# pcb2_0.net
KiCad netlist of a schematic drawn in EAGLE
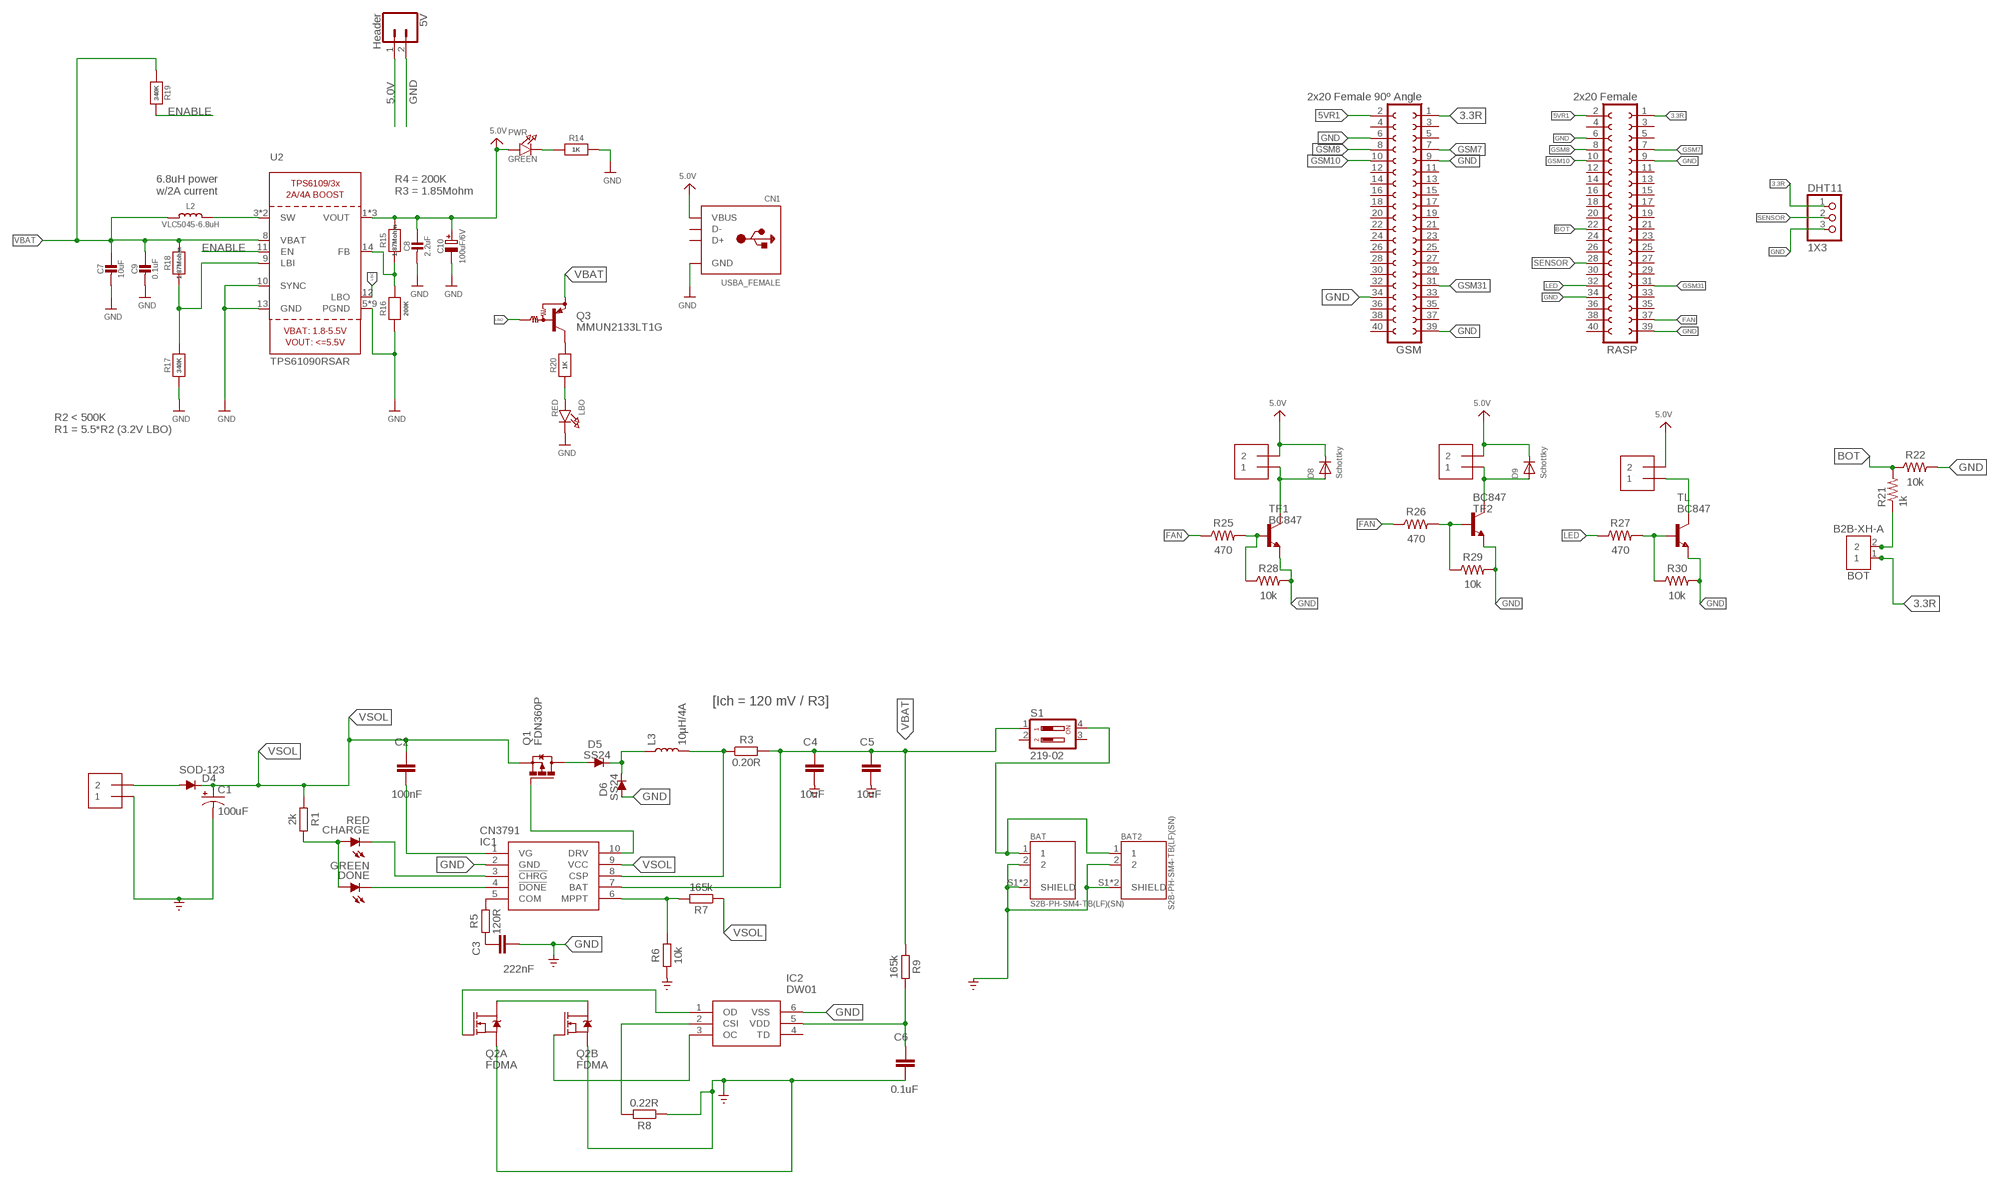
[diagram p0: schematic, sheet 1]

(export (version "E")
  (design (tool "Eeschema 10.0.6"))
  (components
    (comp (ref "5V")
      (value "Header")
      (footprint "eagle-import:1X02")
      (libsource (lib "eagle-import") (part "CONN_02"))
    )
    (comp (ref "BAT")
      (value "S2B-PH-SM4-TB(LF)(SN)")
      (footprint "eagle-import:S2B-PH-SM4-TB(LF)(SN)")
      (fields
        (field (name "DIGI_KEY_PART_NUMBER") "455-1749-1-ND")
        (field (name "MANUFACTURER") "JST Sales America Inc.")
        (field (name "CREATED_BY") "PCBLayout.com")
      )
      (libsource (lib "eagle-import") (part "S2B-PH-SM4-TB(LF)(SN)"))
    )
    (comp (ref "BAT2")
      (value "S2B-PH-SM4-TB(LF)(SN)")
      (footprint "eagle-import:S2B-PH-SM4-TB(LF)(SN)")
      (fields
        (field (name "DIGI_KEY_PART_NUMBER") "455-1749-1-ND")
        (field (name "MANUFACTURER") "JST Sales America Inc.")
        (field (name "CREATED_BY") "PCBLayout.com")
      )
      (libsource (lib "eagle-import") (part "S2B-PH-SM4-TB(LF)(SN)"))
    )
    (comp (ref "BOT")
      (value "B2B-XH-A")
      (footprint "eagle-import:B2B-XH-A")
      (fields (field (name "MANUFACTURER") "JST (XH CONNECTOR)"))
      (libsource (lib "eagle-import") (part "B2B-XH-A"))
    )
    (comp (ref "C1")
      (value "100uF")
      (footprint "eagle-import:153CLV-0505")
      (libsource (lib "eagle-import") (part "CPOL-US153CLV-0505"))
    )
    (comp (ref "C2")
      (value "100nF")
      (footprint "eagle-import:CAP_0603")
      (fields
        (field (name "DIGIKEY_PART_NUMBER") "399-1050-2-ND")
        (field (name "MANUFACTURER") "KEMET")
        (field (name "MPN") "C0603C120J5GACTU")
        (field (name "CREATED_BY") "PCBLayout.com")
      )
      (libsource (lib "eagle-import") (part "C0603C120J5GACTU"))
    )
    (comp (ref "C3")
      (value "222nF")
      (footprint "eagle-import:CAP_0603")
      (fields
        (field (name "DIGIKEY_PART_NUMBER") "399-1050-2-ND")
        (field (name "MANUFACTURER") "KEMET")
        (field (name "MPN") "C0603C120J5GACTU")
        (field (name "CREATED_BY") "PCBLayout.com")
      )
      (libsource (lib "eagle-import") (part "C0603C120J5GACTU"))
    )
    (comp (ref "C4")
      (value "10uF")
      (footprint "eagle-import:CAP_0603")
      (fields
        (field (name "DIGIKEY_PART_NUMBER") "399-1050-2-ND")
        (field (name "MANUFACTURER") "KEMET")
        (field (name "MPN") "C0603C120J5GACTU")
        (field (name "CREATED_BY") "PCBLayout.com")
      )
      (libsource (lib "eagle-import") (part "C0603C120J5GACTU"))
    )
    (comp (ref "C5")
      (value "10uF")
      (footprint "eagle-import:CAP_0603")
      (fields
        (field (name "DIGIKEY_PART_NUMBER") "399-1050-2-ND")
        (field (name "MANUFACTURER") "KEMET")
        (field (name "MPN") "C0603C120J5GACTU")
        (field (name "CREATED_BY") "PCBLayout.com")
      )
      (libsource (lib "eagle-import") (part "C0603C120J5GACTU"))
    )
    (comp (ref "C6")
      (value "0.1uF")
      (footprint "eagle-import:CAP_0603")
      (fields
        (field (name "DIGIKEY_PART_NUMBER") "399-1050-2-ND")
        (field (name "MANUFACTURER") "KEMET")
        (field (name "MPN") "C0603C120J5GACTU")
        (field (name "CREATED_BY") "PCBLayout.com")
      )
      (libsource (lib "eagle-import") (part "C0603C120J5GACTU"))
    )
    (comp (ref "C7")
      (value "10uF")
      (footprint "eagle-import:0805-NO")
      (libsource (lib "eagle-import") (part "CAP_CERAMIC0805-NOOUTLINE"))
    )
    (comp (ref "C8")
      (value "2.2uF")
      (footprint "eagle-import:0805-NO")
      (libsource (lib "eagle-import") (part "CAP_CERAMIC0805-NOOUTLINE"))
    )
    (comp (ref "C9")
      (value "0.1uF")
      (footprint "eagle-import:0805-NO")
      (libsource (lib "eagle-import") (part "CAP_CERAMIC0805-NOOUTLINE"))
    )
    (comp (ref "C10")
      (value "100uF/6V")
      (footprint "eagle-import:EIA3528-21_B-R")
      (libsource (lib "eagle-import") (part "CAP_TANTALUMB/3528_REFLOW"))
    )
    (comp (ref "CHARGE")
      (value "RED")
      (footprint "eagle-import:LED_CHIP-LED0603MP")
      (libsource (lib "eagle-import") (part "LED_LEDCHIP-LED0603MP"))
    )
    (comp (ref "CN1")
      (value "USBA_FEMALE")
      (footprint "eagle-import:USB_HOST-PTH")
      (libsource (lib "eagle-import") (part "USB_TYPEAPTHFML"))
    )
    (comp (ref "D4")
      (value "SOD-123")
      (footprint "eagle-import:DIODE_SOD123")
      (libsource (lib "eagle-import") (part "DIODE_DIODE-SOD123"))
    )
    (comp (ref "D5")
      (value "SS24")
      (footprint "eagle-import:DIODE_SOD123")
      (libsource (lib "eagle-import") (part "DIODE_DIODE-SOD123"))
    )
    (comp (ref "D6")
      (value "SS24")
      (footprint "eagle-import:DIODE_SOD123")
      (libsource (lib "eagle-import") (part "DIODE_DIODE-SOD123"))
    )
    (comp (ref "D8")
      (value "Schottky")
      (footprint "eagle-import:SOD-123")
      (libsource (lib "eagle-import") (part "DIODESOD-123"))
    )
    (comp (ref "D9")
      (value "Schottky")
      (footprint "eagle-import:SOD-123")
      (libsource (lib "eagle-import") (part "DIODESOD-123"))
    )
    (comp (ref "DHT11")
      (value "1X3")
      (footprint "eagle-import:1X03")
      (libsource (lib "eagle-import") (part "PINHD-1X3"))
    )
    (comp (ref "DONE")
      (value "GREEN")
      (footprint "eagle-import:LED_CHIP-LED0603MP")
      (libsource (lib "eagle-import") (part "LED_LEDCHIP-LED0603MP"))
    )
    (comp (ref "FAN1")
      (value "1X2-3.5MM")
      (footprint "eagle-import:1X2-3.5MM")
      (libsource (lib "eagle-import") (part "1X2-3.5MM"))
    )
    (comp (ref "FAN2")
      (value "1X2-3.5MM")
      (footprint "eagle-import:1X2-3.5MM")
      (libsource (lib "eagle-import") (part "1X2-3.5MM"))
    )
    (comp (ref "GSM")
      (value "2x20 Female 90º Angle")
      (footprint "eagle-import:FE20-2W")
      (libsource (lib "eagle-import") (part "FE20-2W"))
    )
    (comp (ref "IC1")
      (value "CN3791")
      (footprint "eagle-import:SOP100P600X175-10N")
      (libsource (lib "eagle-import") (part "CN3791"))
    )
    (comp (ref "IC2")
      (value "DW01")
      (footprint "eagle-import:SOT95P280X135-6N")
      (libsource (lib "eagle-import") (part "DW01"))
    )
    (comp (ref "L2")
      (value "VLC5045-6.8uH")
      (footprint "eagle-import:INDUCTOR_5X5MM_TDK_VLC5045")
      (libsource (lib "eagle-import") (part "INDUCTORTDK_VLC5045"))
    )
    (comp (ref "L3")
      (value "10µH/4A")
      (footprint "eagle-import:CR54")
      (libsource (lib "eagle-import") (part "INDUCTOR-CR54-3.3UH"))
    )
    (comp (ref "LBO")
      (value "RED")
      (footprint "eagle-import:CHIPLED_0805_NOOUTLINE")
      (libsource (lib "eagle-import") (part "LED0805_NOOUTLINE"))
    )
    (comp (ref "LED")
      (value "1X2-3.5MM")
      (footprint "eagle-import:1X2-3.5MM")
      (libsource (lib "eagle-import") (part "1X2-3.5MM"))
    )
    (comp (ref "PWR")
      (value "GREEN")
      (footprint "eagle-import:CHIPLED_0805_NOOUTLINE")
      (libsource (lib "eagle-import") (part "LED0805_NOOUTLINE"))
    )
    (comp (ref "Q1")
      (value "FDN360P")
      (footprint "eagle-import:SUPER-SOT3")
      (libsource (lib "eagle-import") (part "FDN360P"))
    )
    (comp (ref "Q2")
      (value "FDMA")
      (footprint "eagle-import:MICROFET_2X2")
      (libsource (lib "eagle-import") (part "MOSFET_NCH_DUAL-FDMA1024NZ"))
    )
    (comp (ref "Q3")
      (value "MMUN2133LT1G")
      (footprint "eagle-import:SC59-BEC")
      (libsource (lib "eagle-import") (part "-PNP_DRIVER-SC59-BECMUN2114T1"))
    )
    (comp (ref "R1")
      (value "2k")
      (footprint "eagle-import:RESC1608X60")
      (libsource (lib "eagle-import") (part "RCHIP-0603(1608-METRIC)_"))
    )
    (comp (ref "R3")
      (value "0.20R")
      (footprint "eagle-import:RESC1608X60")
      (libsource (lib "eagle-import") (part "RCHIP-0603(1608-METRIC)_"))
    )
    (comp (ref "R5")
      (value "120R")
      (footprint "eagle-import:RESC1608X60")
      (libsource (lib "eagle-import") (part "RCHIP-0603(1608-METRIC)_"))
    )
    (comp (ref "R6")
      (value "10k")
      (footprint "eagle-import:RESC1608X60")
      (libsource (lib "eagle-import") (part "RCHIP-0603(1608-METRIC)_"))
    )
    (comp (ref "R7")
      (value "165k")
      (footprint "eagle-import:RESC1608X60")
      (libsource (lib "eagle-import") (part "RCHIP-0603(1608-METRIC)_"))
    )
    (comp (ref "R8")
      (value "0.22R")
      (footprint "eagle-import:RESC1608X60")
      (libsource (lib "eagle-import") (part "RCHIP-0603(1608-METRIC)_"))
    )
    (comp (ref "R9")
      (value "165k")
      (footprint "eagle-import:RESC1608X60")
      (libsource (lib "eagle-import") (part "RCHIP-0603(1608-METRIC)_"))
    )
    (comp (ref "R14")
      (value "1K")
      (footprint "eagle-import:0805-NO")
      (libsource (lib "eagle-import") (part "RESISTOR0805_NOOUTLINE"))
    )
    (comp (ref "R15")
      (value "1.87Mohm")
      (footprint "eagle-import:0805-NO")
      (libsource (lib "eagle-import") (part "RESISTOR0805_NOOUTLINE"))
    )
    (comp (ref "R16")
      (value "200K")
      (footprint "eagle-import:0805-NO")
      (libsource (lib "eagle-import") (part "RESISTOR0805_NOOUTLINE"))
    )
    (comp (ref "R17")
      (value "340K")
      (footprint "eagle-import:0805-NO")
      (libsource (lib "eagle-import") (part "RESISTOR0805_NOOUTLINE"))
    )
    (comp (ref "R18")
      (value "1.87Mohm")
      (footprint "eagle-import:0805-NO")
      (libsource (lib "eagle-import") (part "RESISTOR0805_NOOUTLINE"))
    )
    (comp (ref "R19")
      (value "340K")
      (footprint "eagle-import:0805-NO")
      (libsource (lib "eagle-import") (part "RESISTOR0805_NOOUTLINE"))
    )
    (comp (ref "R20")
      (value "1K")
      (footprint "eagle-import:0805-NO")
      (libsource (lib "eagle-import") (part "RESISTOR0805_NOOUTLINE"))
    )
    (comp (ref "R21")
      (value "1k")
      (footprint "eagle-import:R0805")
      (libsource (lib "eagle-import") (part "R-US_R0805"))
    )
    (comp (ref "R22")
      (value "10k")
      (footprint "eagle-import:RESC2012X65")
      (libsource (lib "eagle-import") (part "R-USCHIP-0805(2012-METRIC)_"))
    )
    (comp (ref "R25")
      (value "470")
      (footprint "eagle-import:RESC2012X65")
      (libsource (lib "eagle-import") (part "R-USCHIP-0805(2012-METRIC)_"))
    )
    (comp (ref "R26")
      (value "470")
      (footprint "eagle-import:RESC2012X65")
      (libsource (lib "eagle-import") (part "R-USCHIP-0805(2012-METRIC)_"))
    )
    (comp (ref "R27")
      (value "470")
      (footprint "eagle-import:RESC2012X65")
      (libsource (lib "eagle-import") (part "R-USCHIP-0805(2012-METRIC)_"))
    )
    (comp (ref "R28")
      (value "10k")
      (footprint "eagle-import:RESC2012X65")
      (libsource (lib "eagle-import") (part "R-USCHIP-0805(2012-METRIC)_"))
    )
    (comp (ref "R29")
      (value "10k")
      (footprint "eagle-import:RESC2012X65")
      (libsource (lib "eagle-import") (part "R-USCHIP-0805(2012-METRIC)_"))
    )
    (comp (ref "R30")
      (value "10k")
      (footprint "eagle-import:RESC2012X65")
      (libsource (lib "eagle-import") (part "R-USCHIP-0805(2012-METRIC)_"))
    )
    (comp (ref "RASP")
      (value "2x20 Female")
      (footprint "eagle-import:FE20-2")
      (libsource (lib "eagle-import") (part "FE20-2"))
    )
    (comp (ref "S1")
      (value "219-02")
      (footprint "eagle-import:CTS-219-02")
      (libsource (lib "eagle-import") (part "219-02"))
    )
    (comp (ref "TF1")
      (value "BC847")
      (footprint "eagle-import:SOT23")
      (libsource (lib "eagle-import") (part "BC847"))
    )
    (comp (ref "TF2")
      (value "BC847")
      (footprint "eagle-import:SOT23")
      (libsource (lib "eagle-import") (part "BC847"))
    )
    (comp (ref "TL")
      (value "BC847")
      (footprint "eagle-import:SOT23")
      (libsource (lib "eagle-import") (part "BC847"))
    )
    (comp (ref "U2")
      (value "TPS61090RSAR")
      (footprint "eagle-import:PVQFN-16")
      (libsource (lib "eagle-import") (part "VREG_TPS6103X"))
    )
    (comp (ref "VIN")
      (value "1X2-3.5MM")
      (footprint "eagle-import:1X2-3.5MM")
      (libsource (lib "eagle-import") (part "1X2-3.5MM"))
    )
  )
  (nets
    (net (code "1") (name "/ENABLE") (class "Default")
      (node (ref "R19") (pin "2") (pinfunction "2_2") (pintype "passive"))
      (node (ref "U2") (pin "11") (pinfunction "EN_11") (pintype "input"))
    )
    (net (code "2") (name "3.3R") (class "Default")
      (node (ref "BOT") (pin "1") (pinfunction "1_1") (pintype "bidirectional"))
      (node (ref "DHT11") (pin "1") (pinfunction "1_1") (pintype "passive"))
      (node (ref "GSM") (pin "1") (pinfunction "1_1") (pintype "passive"))
      (node (ref "RASP") (pin "1") (pinfunction "1_1") (pintype "passive"))
    )
    (net (code "3") (name "5.0V") (class "Default")
      (node (ref "5V") (pin "1") (pinfunction "1_1") (pintype "passive"))
      (node (ref "C10") (pin "+") (pinfunction "+_+") (pintype "passive"))
      (node (ref "C8") (pin "1") (pinfunction "1_1") (pintype "passive"))
      (node (ref "CN1") (pin "VBUS") (pinfunction "VBUS_VBUS") (pintype "power_in"))
      (node (ref "D8") (pin "C") (pinfunction "C_C") (pintype "passive"))
      (node (ref "D9") (pin "C") (pinfunction "C_C") (pintype "passive"))
      (node (ref "FAN1") (pin "2") (pinfunction "2_2") (pintype "passive"))
      (node (ref "FAN2") (pin "2") (pinfunction "2_2") (pintype "passive"))
      (node (ref "LED") (pin "2") (pinfunction "2_2") (pintype "passive"))
      (node (ref "PWR") (pin "A") (pinfunction "A_A") (pintype "passive"))
      (node (ref "R15") (pin "2") (pinfunction "2_2") (pintype "passive"))
      (node (ref "U2") (pin "1") (pinfunction "VOUT_1") (pintype "power_in"))
      (node (ref "U2") (pin "15") (pinfunction "VOUT_15") (pintype "power_in"))
      (node (ref "U2") (pin "16") (pinfunction "VOUT_16") (pintype "power_in"))
    )
    (net (code "4") (name "5VR1") (class "Default")
      (node (ref "GSM") (pin "2") (pinfunction "2_2") (pintype "passive"))
      (node (ref "RASP") (pin "2") (pinfunction "2_2") (pintype "passive"))
    )
    (net (code "5") (name "BOT") (class "Default")
      (node (ref "R21") (pin "2") (pinfunction "2_2") (pintype "passive"))
      (node (ref "R22") (pin "1") (pinfunction "1_1") (pintype "passive"))
      (node (ref "RASP") (pin "22") (pinfunction "22_22") (pintype "passive"))
    )
    (net (code "6") (name "FAN") (class "Default")
      (node (ref "R25") (pin "1") (pinfunction "1_1") (pintype "passive"))
      (node (ref "R26") (pin "1") (pinfunction "1_1") (pintype "passive"))
      (node (ref "RASP") (pin "37") (pinfunction "37_37") (pintype "passive"))
    )
    (net (code "7") (name "GND") (class "Default")
      (node (ref "5V") (pin "2") (pinfunction "2_2") (pintype "passive"))
      (node (ref "BAT") (pin "2") (pinfunction "2_2") (pintype "passive"))
      (node (ref "BAT") (pin "S1") (pinfunction "SHIELD_S1") (pintype "passive"))
      (node (ref "BAT") (pin "S2") (pinfunction "SHIELD_S2") (pintype "passive"))
      (node (ref "BAT2") (pin "2") (pinfunction "2_2") (pintype "passive"))
      (node (ref "BAT2") (pin "S1") (pinfunction "SHIELD_S1") (pintype "passive"))
      (node (ref "BAT2") (pin "S2") (pinfunction "SHIELD_S2") (pintype "passive"))
      (node (ref "C1") (pin "-") (pinfunction "-_-") (pintype "passive"))
      (node (ref "C10") (pin "-") (pinfunction "-_-") (pintype "passive"))
      (node (ref "C3") (pin "2") (pinfunction "2_2") (pintype "passive"))
      (node (ref "C4") (pin "2") (pinfunction "2_2") (pintype "passive"))
      (node (ref "C5") (pin "2") (pinfunction "2_2") (pintype "passive"))
      (node (ref "C6") (pin "2") (pinfunction "2_2") (pintype "passive"))
      (node (ref "C7") (pin "2") (pinfunction "2_2") (pintype "passive"))
      (node (ref "C8") (pin "2") (pinfunction "2_2") (pintype "passive"))
      (node (ref "C9") (pin "2") (pinfunction "2_2") (pintype "passive"))
      (node (ref "CN1") (pin "GND") (pinfunction "GND_GND") (pintype "power_in"))
      (node (ref "D6") (pin "A") (pinfunction "A_A") (pintype "passive"))
      (node (ref "DHT11") (pin "3") (pinfunction "3_3") (pintype "passive"))
      (node (ref "GSM") (pin "34") (pinfunction "34_34") (pintype "passive"))
      (node (ref "GSM") (pin "39") (pinfunction "39_39") (pintype "passive"))
      (node (ref "GSM") (pin "6") (pinfunction "6_6") (pintype "passive"))
      (node (ref "GSM") (pin "9") (pinfunction "9_9") (pintype "passive"))
      (node (ref "IC1") (pin "2") (pinfunction "GND_2") (pintype "bidirectional"))
      (node (ref "IC2") (pin "6") (pinfunction "VSS_6") (pintype "bidirectional"))
      (node (ref "LBO") (pin "C") (pinfunction "C_C") (pintype "passive"))
      (node (ref "Q2") (pin "S1") (pinfunction "S_S1") (pintype "bidirectional"))
      (node (ref "Q2") (pin "S2") (pinfunction "S_S2") (pintype "bidirectional"))
      (node (ref "R14") (pin "2") (pinfunction "2_2") (pintype "passive"))
      (node (ref "R16") (pin "1") (pinfunction "1_1") (pintype "passive"))
      (node (ref "R17") (pin "1") (pinfunction "1_1") (pintype "passive"))
      (node (ref "R22") (pin "2") (pinfunction "2_2") (pintype "passive"))
      (node (ref "R28") (pin "2") (pinfunction "2_2") (pintype "passive"))
      (node (ref "R29") (pin "2") (pinfunction "2_2") (pintype "passive"))
      (node (ref "R30") (pin "2") (pinfunction "2_2") (pintype "passive"))
      (node (ref "R6") (pin "1") (pinfunction "1_1") (pintype "passive"))
      (node (ref "R8") (pin "1") (pinfunction "1_1") (pintype "passive"))
      (node (ref "RASP") (pin "34") (pinfunction "34_34") (pintype "passive"))
      (node (ref "RASP") (pin "39") (pinfunction "39_39") (pintype "passive"))
      (node (ref "RASP") (pin "6") (pinfunction "6_6") (pintype "passive"))
      (node (ref "RASP") (pin "9") (pinfunction "9_9") (pintype "passive"))
      (node (ref "TF1") (pin "2") (pinfunction "E_2") (pintype "passive"))
      (node (ref "TF2") (pin "2") (pinfunction "E_2") (pintype "passive"))
      (node (ref "TL") (pin "2") (pinfunction "E_2") (pintype "passive"))
      (node (ref "U2") (pin "10") (pinfunction "SYNC_10") (pintype "input"))
      (node (ref "U2") (pin "13") (pinfunction "GND_13") (pintype "power_in"))
      (node (ref "U2") (pin "5") (pinfunction "PGND_5") (pintype "power_in"))
      (node (ref "U2") (pin "6") (pinfunction "PGND_6") (pintype "power_in"))
      (node (ref "U2") (pin "7") (pinfunction "PGND_7") (pintype "power_in"))
      (node (ref "U2") (pin "P$18") (pinfunction "PGND_P$18") (pintype "power_in"))
      (node (ref "U2") (pin "P$19") (pinfunction "PGND_P$19") (pintype "power_in"))
      (node (ref "U2") (pin "P$20") (pinfunction "PGND_P$20") (pintype "power_in"))
      (node (ref "U2") (pin "P$21") (pinfunction "PGND_P$21") (pintype "power_in"))
      (node (ref "U2") (pin "P$22") (pinfunction "PGND_P$22") (pintype "power_in"))
      (node (ref "U2") (pin "THERMAL") (pinfunction "PGND_THERMAL") (pintype "power_in"))
      (node (ref "VIN") (pin "1") (pinfunction "1_1") (pintype "passive"))
    )
    (net (code "8") (name "GSM7") (class "Default")
      (node (ref "GSM") (pin "7") (pinfunction "7_7") (pintype "passive"))
      (node (ref "RASP") (pin "7") (pinfunction "7_7") (pintype "passive"))
    )
    (net (code "9") (name "GSM8") (class "Default")
      (node (ref "GSM") (pin "8") (pinfunction "8_8") (pintype "passive"))
      (node (ref "RASP") (pin "8") (pinfunction "8_8") (pintype "passive"))
    )
    (net (code "10") (name "GSM10") (class "Default")
      (node (ref "GSM") (pin "10") (pinfunction "10_10") (pintype "passive"))
      (node (ref "RASP") (pin "10") (pinfunction "10_10") (pintype "passive"))
    )
    (net (code "11") (name "GSM31") (class "Default")
      (node (ref "GSM") (pin "31") (pinfunction "31_31") (pintype "passive"))
      (node (ref "RASP") (pin "31") (pinfunction "31_31") (pintype "passive"))
    )
    (net (code "12") (name "LBO") (class "Default")
      (node (ref "Q3") (pin "B") (pinfunction "B_B") (pintype "passive"))
      (node (ref "U2") (pin "12") (pinfunction "LBO_12") (pintype "output"))
    )
    (net (code "13") (name "LED") (class "Default")
      (node (ref "R27") (pin "1") (pinfunction "1_1") (pintype "passive"))
      (node (ref "RASP") (pin "32") (pinfunction "32_32") (pintype "passive"))
    )
    (net (code "14") (name "Net-(BAT-Pad1)") (class "Default")
      (node (ref "BAT") (pin "1") (pinfunction "1_1") (pintype "passive"))
      (node (ref "BAT2") (pin "1") (pinfunction "1_1") (pintype "passive"))
      (node (ref "S1") (pin "4") (pinfunction "4_4") (pintype "passive"))
    )
    (net (code "15") (name "Net-(BOT-Pad2)") (class "Default")
      (node (ref "BOT") (pin "2") (pinfunction "2_2") (pintype "bidirectional"))
      (node (ref "R21") (pin "1") (pinfunction "1_1") (pintype "passive"))
    )
    (net (code "16") (name "Net-(C3-Pad1)") (class "Default")
      (node (ref "C3") (pin "1") (pinfunction "1_1") (pintype "passive"))
      (node (ref "R5") (pin "1") (pinfunction "1_1") (pintype "passive"))
    )
    (net (code "17") (name "Net-(CHARGE-PadA)") (class "Default")
      (node (ref "CHARGE") (pin "A") (pinfunction "A_A") (pintype "passive"))
      (node (ref "DONE") (pin "A") (pinfunction "A_A") (pintype "passive"))
      (node (ref "R1") (pin "2") (pinfunction "2_2") (pintype "passive"))
    )
    (net (code "18") (name "Net-(D4-PadA)") (class "Default")
      (node (ref "D4") (pin "A") (pinfunction "A_A") (pintype "passive"))
      (node (ref "VIN") (pin "2") (pinfunction "2_2") (pintype "passive"))
    )
    (net (code "19") (name "Net-(IC1-COM)") (class "Default")
      (node (ref "IC1") (pin "5") (pinfunction "COM_5") (pintype "bidirectional"))
      (node (ref "R5") (pin "2") (pinfunction "2_2") (pintype "passive"))
    )
    (net (code "20") (name "Net-(IC1-CSP)") (class "Default")
      (node (ref "IC1") (pin "8") (pinfunction "CSP_8") (pintype "bidirectional"))
      (node (ref "L3") (pin "P$2") (pinfunction "2_P$2") (pintype "passive"))
      (node (ref "R3") (pin "1") (pinfunction "1_1") (pintype "passive"))
    )
    (net (code "21") (name "Net-(IC1-DRV)") (class "Default")
      (node (ref "IC1") (pin "10") (pinfunction "DRV_10") (pintype "bidirectional"))
      (node (ref "Q1") (pin "1") (pinfunction "G_1") (pintype "passive"))
    )
    (net (code "22") (name "Net-(IC1-MPPT)") (class "Default")
      (node (ref "IC1") (pin "6") (pinfunction "MPPT_6") (pintype "bidirectional"))
      (node (ref "R6") (pin "2") (pinfunction "2_2") (pintype "passive"))
      (node (ref "R7") (pin "2") (pinfunction "2_2") (pintype "passive"))
    )
    (net (code "23") (name "Net-(IC1-VG)") (class "Default")
      (node (ref "C2") (pin "2") (pinfunction "2_2") (pintype "passive"))
      (node (ref "IC1") (pin "1") (pinfunction "VG_1") (pintype "bidirectional"))
    )
    (net (code "24") (name "Net-(IC1-~{CHRG})") (class "Default")
      (node (ref "CHARGE") (pin "C") (pinfunction "C_C") (pintype "passive"))
      (node (ref "IC1") (pin "3") (pinfunction "~{CHRG}_3") (pintype "bidirectional"))
    )
    (net (code "25") (name "Net-(IC1-~{DONE})") (class "Default")
      (node (ref "DONE") (pin "C") (pinfunction "C_C") (pintype "passive"))
      (node (ref "IC1") (pin "4") (pinfunction "~{DONE}_4") (pintype "bidirectional"))
    )
    (net (code "26") (name "Net-(IC2-CSI)") (class "Default")
      (node (ref "IC2") (pin "2") (pinfunction "CSI_2") (pintype "bidirectional"))
      (node (ref "R8") (pin "2") (pinfunction "2_2") (pintype "passive"))
    )
    (net (code "27") (name "Net-(IC2-OC)") (class "Default")
      (node (ref "IC2") (pin "3") (pinfunction "OC_3") (pintype "bidirectional"))
      (node (ref "Q2") (pin "G2") (pinfunction "G_G2") (pintype "bidirectional"))
    )
    (net (code "28") (name "Net-(IC2-OD)") (class "Default")
      (node (ref "IC2") (pin "1") (pinfunction "OD_1") (pintype "bidirectional"))
      (node (ref "Q2") (pin "G1") (pinfunction "G_G1") (pintype "bidirectional"))
    )
    (net (code "29") (name "Net-(IC2-VDD)") (class "Default")
      (node (ref "C6") (pin "1") (pinfunction "1_1") (pintype "passive"))
      (node (ref "IC2") (pin "5") (pinfunction "VDD_5") (pintype "bidirectional"))
      (node (ref "R9") (pin "2") (pinfunction "2_2") (pintype "passive"))
    )
    (net (code "30") (name "Net-(L2-2)") (class "Default")
      (node (ref "L2") (pin "P$2") (pinfunction "2_P$2") (pintype "passive"))
      (node (ref "U2") (pin "3") (pinfunction "SW_3") (pintype "input"))
      (node (ref "U2") (pin "4") (pinfunction "SW_4") (pintype "input"))
    )
    (net (code "31") (name "Net-(L3-1)") (class "Default")
      (node (ref "D5") (pin "C") (pinfunction "C_C") (pintype "passive"))
      (node (ref "D6") (pin "C") (pinfunction "C_C") (pintype "passive"))
      (node (ref "L3") (pin "P$1") (pinfunction "1_P$1") (pintype "passive"))
    )
    (net (code "32") (name "Net-(LBO-PadA)") (class "Default")
      (node (ref "LBO") (pin "A") (pinfunction "A_A") (pintype "passive"))
      (node (ref "R20") (pin "1") (pinfunction "1_1") (pintype "passive"))
    )
    (net (code "33") (name "Net-(PWR-PadC)") (class "Default")
      (node (ref "PWR") (pin "C") (pinfunction "C_C") (pintype "passive"))
      (node (ref "R14") (pin "1") (pinfunction "1_1") (pintype "passive"))
    )
    (net (code "34") (name "Net-(Q1-D)") (class "Default")
      (node (ref "D5") (pin "A") (pinfunction "A_A") (pintype "passive"))
      (node (ref "Q1") (pin "3") (pinfunction "D_3") (pintype "passive"))
    )
    (net (code "35") (name "Net-(Q2A-D-PadD1)") (class "Default")
      (node (ref "Q2") (pin "D1") (pinfunction "D_D1") (pintype "bidirectional"))
      (node (ref "Q2") (pin "D1_2") (pinfunction "D_D1_2") (pintype "bidirectional"))
      (node (ref "Q2") (pin "D2") (pinfunction "D_D2") (pintype "bidirectional"))
      (node (ref "Q2") (pin "D2_2") (pinfunction "D_D2_2") (pintype "bidirectional"))
    )
    (net (code "36") (name "Net-(Q3-PadC)") (class "Default")
      (node (ref "Q3") (pin "C") (pinfunction "C_C") (pintype "passive"))
      (node (ref "R20") (pin "2") (pinfunction "2_2") (pintype "passive"))
    )
    (net (code "37") (name "Net-(TF1-B)") (class "Default")
      (node (ref "R25") (pin "2") (pinfunction "2_2") (pintype "passive"))
      (node (ref "R28") (pin "1") (pinfunction "1_1") (pintype "passive"))
      (node (ref "TF1") (pin "1") (pinfunction "B_1") (pintype "passive"))
    )
    (net (code "38") (name "Net-(TF1-C)") (class "Default")
      (node (ref "D8") (pin "A") (pinfunction "A_A") (pintype "passive"))
      (node (ref "FAN1") (pin "1") (pinfunction "1_1") (pintype "passive"))
      (node (ref "TF1") (pin "3") (pinfunction "C_3") (pintype "passive"))
    )
    (net (code "39") (name "Net-(TF2-B)") (class "Default")
      (node (ref "R26") (pin "2") (pinfunction "2_2") (pintype "passive"))
      (node (ref "R29") (pin "1") (pinfunction "1_1") (pintype "passive"))
      (node (ref "TF2") (pin "1") (pinfunction "B_1") (pintype "passive"))
    )
    (net (code "40") (name "Net-(TF2-C)") (class "Default")
      (node (ref "D9") (pin "A") (pinfunction "A_A") (pintype "passive"))
      (node (ref "FAN2") (pin "1") (pinfunction "1_1") (pintype "passive"))
      (node (ref "TF2") (pin "3") (pinfunction "C_3") (pintype "passive"))
    )
    (net (code "41") (name "Net-(TL-B)") (class "Default")
      (node (ref "R27") (pin "2") (pinfunction "2_2") (pintype "passive"))
      (node (ref "R30") (pin "1") (pinfunction "1_1") (pintype "passive"))
      (node (ref "TL") (pin "1") (pinfunction "B_1") (pintype "passive"))
    )
    (net (code "42") (name "Net-(TL-C)") (class "Default")
      (node (ref "LED") (pin "1") (pinfunction "1_1") (pintype "passive"))
      (node (ref "TL") (pin "3") (pinfunction "C_3") (pintype "passive"))
    )
    (net (code "43") (name "Net-(U2-FB)") (class "Default")
      (node (ref "R15") (pin "1") (pinfunction "1_1") (pintype "passive"))
      (node (ref "R16") (pin "2") (pinfunction "2_2") (pintype "passive"))
      (node (ref "U2") (pin "14") (pinfunction "FB_14") (pintype "input"))
    )
    (net (code "44") (name "Net-(U2-LBI)") (class "Default")
      (node (ref "R17") (pin "2") (pinfunction "2_2") (pintype "passive"))
      (node (ref "R18") (pin "1") (pinfunction "1_1") (pintype "passive"))
      (node (ref "U2") (pin "9") (pinfunction "LBI_9") (pintype "input"))
    )
    (net (code "45") (name "SENSOR") (class "Default")
      (node (ref "DHT11") (pin "2") (pinfunction "2_2") (pintype "passive"))
      (node (ref "RASP") (pin "28") (pinfunction "28_28") (pintype "passive"))
    )
    (net (code "46") (name "VBAT") (class "Default")
      (node (ref "C4") (pin "1") (pinfunction "1_1") (pintype "passive"))
      (node (ref "C5") (pin "1") (pinfunction "1_1") (pintype "passive"))
      (node (ref "C7") (pin "1") (pinfunction "1_1") (pintype "passive"))
      (node (ref "C9") (pin "1") (pinfunction "1_1") (pintype "passive"))
      (node (ref "IC1") (pin "7") (pinfunction "BAT_7") (pintype "bidirectional"))
      (node (ref "L2") (pin "P$1") (pinfunction "1_P$1") (pintype "passive"))
      (node (ref "Q3") (pin "E") (pinfunction "E_E") (pintype "passive"))
      (node (ref "R18") (pin "2") (pinfunction "2_2") (pintype "passive"))
      (node (ref "R19") (pin "1") (pinfunction "1_1") (pintype "passive"))
      (node (ref "R3") (pin "2") (pinfunction "2_2") (pintype "passive"))
      (node (ref "R9") (pin "1") (pinfunction "1_1") (pintype "passive"))
      (node (ref "S1") (pin "1") (pinfunction "1_1") (pintype "passive"))
      (node (ref "U2") (pin "8") (pinfunction "VBAT_8") (pintype "input"))
    )
    (net (code "47") (name "VSOL") (class "Default")
      (node (ref "C1") (pin "+") (pinfunction "+_+") (pintype "passive"))
      (node (ref "C2") (pin "1") (pinfunction "1_1") (pintype "passive"))
      (node (ref "D4") (pin "C") (pinfunction "C_C") (pintype "passive"))
      (node (ref "IC1") (pin "9") (pinfunction "VCC_9") (pintype "bidirectional"))
      (node (ref "Q1") (pin "2") (pinfunction "S_2") (pintype "passive"))
      (node (ref "R1") (pin "1") (pinfunction "1_1") (pintype "passive"))
      (node (ref "R7") (pin "1") (pinfunction "1_1") (pintype "passive"))
    )
    (net (code "48") (name "unconnected-(CN1-PadD+)") (class "Default")
      (node (ref "CN1") (pin "D+") (pinfunction "D+_D+") (pintype "bidirectional"))
    )
    (net (code "49") (name "unconnected-(CN1-PadD-)") (class "Default")
      (node (ref "CN1") (pin "D-") (pinfunction "D-_D-") (pintype "bidirectional"))
    )
    (net (code "50") (name "unconnected-(GSM-Pad3)") (class "Default")
      (node (ref "GSM") (pin "3") (pinfunction "3_3") (pintype "passive"))
    )
    (net (code "51") (name "unconnected-(GSM-Pad4)") (class "Default")
      (node (ref "GSM") (pin "4") (pinfunction "4_4") (pintype "passive"))
    )
    (net (code "52") (name "unconnected-(GSM-Pad5)") (class "Default")
      (node (ref "GSM") (pin "5") (pinfunction "5_5") (pintype "passive"))
    )
    (net (code "53") (name "unconnected-(GSM-Pad11)") (class "Default")
      (node (ref "GSM") (pin "11") (pinfunction "11_11") (pintype "passive"))
    )
    (net (code "54") (name "unconnected-(GSM-Pad12)") (class "Default")
      (node (ref "GSM") (pin "12") (pinfunction "12_12") (pintype "passive"))
    )
    (net (code "55") (name "unconnected-(GSM-Pad13)") (class "Default")
      (node (ref "GSM") (pin "13") (pinfunction "13_13") (pintype "passive"))
    )
    (net (code "56") (name "unconnected-(GSM-Pad14)") (class "Default")
      (node (ref "GSM") (pin "14") (pinfunction "14_14") (pintype "passive"))
    )
    (net (code "57") (name "unconnected-(GSM-Pad15)") (class "Default")
      (node (ref "GSM") (pin "15") (pinfunction "15_15") (pintype "passive"))
    )
    (net (code "58") (name "unconnected-(GSM-Pad16)") (class "Default")
      (node (ref "GSM") (pin "16") (pinfunction "16_16") (pintype "passive"))
    )
    (net (code "59") (name "unconnected-(GSM-Pad17)") (class "Default")
      (node (ref "GSM") (pin "17") (pinfunction "17_17") (pintype "passive"))
    )
    (net (code "60") (name "unconnected-(GSM-Pad18)") (class "Default")
      (node (ref "GSM") (pin "18") (pinfunction "18_18") (pintype "passive"))
    )
    (net (code "61") (name "unconnected-(GSM-Pad19)") (class "Default")
      (node (ref "GSM") (pin "19") (pinfunction "19_19") (pintype "passive"))
    )
    (net (code "62") (name "unconnected-(GSM-Pad20)") (class "Default")
      (node (ref "GSM") (pin "20") (pinfunction "20_20") (pintype "passive"))
    )
    (net (code "63") (name "unconnected-(GSM-Pad21)") (class "Default")
      (node (ref "GSM") (pin "21") (pinfunction "21_21") (pintype "passive"))
    )
    (net (code "64") (name "unconnected-(GSM-Pad22)") (class "Default")
      (node (ref "GSM") (pin "22") (pinfunction "22_22") (pintype "passive"))
    )
    (net (code "65") (name "unconnected-(GSM-Pad23)") (class "Default")
      (node (ref "GSM") (pin "23") (pinfunction "23_23") (pintype "passive"))
    )
    (net (code "66") (name "unconnected-(GSM-Pad24)") (class "Default")
      (node (ref "GSM") (pin "24") (pinfunction "24_24") (pintype "passive"))
    )
    (net (code "67") (name "unconnected-(GSM-Pad25)") (class "Default")
      (node (ref "GSM") (pin "25") (pinfunction "25_25") (pintype "passive"))
    )
    (net (code "68") (name "unconnected-(GSM-Pad26)") (class "Default")
      (node (ref "GSM") (pin "26") (pinfunction "26_26") (pintype "passive"))
    )
    (net (code "69") (name "unconnected-(GSM-Pad27)") (class "Default")
      (node (ref "GSM") (pin "27") (pinfunction "27_27") (pintype "passive"))
    )
    (net (code "70") (name "unconnected-(GSM-Pad28)") (class "Default")
      (node (ref "GSM") (pin "28") (pinfunction "28_28") (pintype "passive"))
    )
    (net (code "71") (name "unconnected-(GSM-Pad29)") (class "Default")
      (node (ref "GSM") (pin "29") (pinfunction "29_29") (pintype "passive"))
    )
    (net (code "72") (name "unconnected-(GSM-Pad30)") (class "Default")
      (node (ref "GSM") (pin "30") (pinfunction "30_30") (pintype "passive"))
    )
    (net (code "73") (name "unconnected-(GSM-Pad32)") (class "Default")
      (node (ref "GSM") (pin "32") (pinfunction "32_32") (pintype "passive"))
    )
    (net (code "74") (name "unconnected-(GSM-Pad33)") (class "Default")
      (node (ref "GSM") (pin "33") (pinfunction "33_33") (pintype "passive"))
    )
    (net (code "75") (name "unconnected-(GSM-Pad35)") (class "Default")
      (node (ref "GSM") (pin "35") (pinfunction "35_35") (pintype "passive"))
    )
    (net (code "76") (name "unconnected-(GSM-Pad36)") (class "Default")
      (node (ref "GSM") (pin "36") (pinfunction "36_36") (pintype "passive"))
    )
    (net (code "77") (name "unconnected-(GSM-Pad37)") (class "Default")
      (node (ref "GSM") (pin "37") (pinfunction "37_37") (pintype "passive"))
    )
    (net (code "78") (name "unconnected-(GSM-Pad38)") (class "Default")
      (node (ref "GSM") (pin "38") (pinfunction "38_38") (pintype "passive"))
    )
    (net (code "79") (name "unconnected-(GSM-Pad40)") (class "Default")
      (node (ref "GSM") (pin "40") (pinfunction "40_40") (pintype "passive"))
    )
    (net (code "80") (name "unconnected-(IC2-TD-Pad4)") (class "Default")
      (node (ref "IC2") (pin "4") (pinfunction "TD_4") (pintype "bidirectional"))
    )
    (net (code "81") (name "unconnected-(RASP-Pad3)") (class "Default")
      (node (ref "RASP") (pin "3") (pinfunction "3_3") (pintype "passive"))
    )
    (net (code "82") (name "unconnected-(RASP-Pad4)") (class "Default")
      (node (ref "RASP") (pin "4") (pinfunction "4_4") (pintype "passive"))
    )
    (net (code "83") (name "unconnected-(RASP-Pad5)") (class "Default")
      (node (ref "RASP") (pin "5") (pinfunction "5_5") (pintype "passive"))
    )
    (net (code "84") (name "unconnected-(RASP-Pad11)") (class "Default")
      (node (ref "RASP") (pin "11") (pinfunction "11_11") (pintype "passive"))
    )
    (net (code "85") (name "unconnected-(RASP-Pad12)") (class "Default")
      (node (ref "RASP") (pin "12") (pinfunction "12_12") (pintype "passive"))
    )
    (net (code "86") (name "unconnected-(RASP-Pad13)") (class "Default")
      (node (ref "RASP") (pin "13") (pinfunction "13_13") (pintype "passive"))
    )
    (net (code "87") (name "unconnected-(RASP-Pad14)") (class "Default")
      (node (ref "RASP") (pin "14") (pinfunction "14_14") (pintype "passive"))
    )
    (net (code "88") (name "unconnected-(RASP-Pad15)") (class "Default")
      (node (ref "RASP") (pin "15") (pinfunction "15_15") (pintype "passive"))
    )
    (net (code "89") (name "unconnected-(RASP-Pad16)") (class "Default")
      (node (ref "RASP") (pin "16") (pinfunction "16_16") (pintype "passive"))
    )
    (net (code "90") (name "unconnected-(RASP-Pad17)") (class "Default")
      (node (ref "RASP") (pin "17") (pinfunction "17_17") (pintype "passive"))
    )
    (net (code "91") (name "unconnected-(RASP-Pad18)") (class "Default")
      (node (ref "RASP") (pin "18") (pinfunction "18_18") (pintype "passive"))
    )
    (net (code "92") (name "unconnected-(RASP-Pad19)") (class "Default")
      (node (ref "RASP") (pin "19") (pinfunction "19_19") (pintype "passive"))
    )
    (net (code "93") (name "unconnected-(RASP-Pad20)") (class "Default")
      (node (ref "RASP") (pin "20") (pinfunction "20_20") (pintype "passive"))
    )
    (net (code "94") (name "unconnected-(RASP-Pad21)") (class "Default")
      (node (ref "RASP") (pin "21") (pinfunction "21_21") (pintype "passive"))
    )
    (net (code "95") (name "unconnected-(RASP-Pad23)") (class "Default")
      (node (ref "RASP") (pin "23") (pinfunction "23_23") (pintype "passive"))
    )
    (net (code "96") (name "unconnected-(RASP-Pad24)") (class "Default")
      (node (ref "RASP") (pin "24") (pinfunction "24_24") (pintype "passive"))
    )
    (net (code "97") (name "unconnected-(RASP-Pad25)") (class "Default")
      (node (ref "RASP") (pin "25") (pinfunction "25_25") (pintype "passive"))
    )
    (net (code "98") (name "unconnected-(RASP-Pad26)") (class "Default")
      (node (ref "RASP") (pin "26") (pinfunction "26_26") (pintype "passive"))
    )
    (net (code "99") (name "unconnected-(RASP-Pad27)") (class "Default")
      (node (ref "RASP") (pin "27") (pinfunction "27_27") (pintype "passive"))
    )
    (net (code "100") (name "unconnected-(RASP-Pad29)") (class "Default")
      (node (ref "RASP") (pin "29") (pinfunction "29_29") (pintype "passive"))
    )
    (net (code "101") (name "unconnected-(RASP-Pad30)") (class "Default")
      (node (ref "RASP") (pin "30") (pinfunction "30_30") (pintype "passive"))
    )
    (net (code "102") (name "unconnected-(RASP-Pad33)") (class "Default")
      (node (ref "RASP") (pin "33") (pinfunction "33_33") (pintype "passive"))
    )
    (net (code "103") (name "unconnected-(RASP-Pad35)") (class "Default")
      (node (ref "RASP") (pin "35") (pinfunction "35_35") (pintype "passive"))
    )
    (net (code "104") (name "unconnected-(RASP-Pad36)") (class "Default")
      (node (ref "RASP") (pin "36") (pinfunction "36_36") (pintype "passive"))
    )
    (net (code "105") (name "unconnected-(RASP-Pad38)") (class "Default")
      (node (ref "RASP") (pin "38") (pinfunction "38_38") (pintype "passive"))
    )
    (net (code "106") (name "unconnected-(RASP-Pad40)") (class "Default")
      (node (ref "RASP") (pin "40") (pinfunction "40_40") (pintype "passive"))
    )
    (net (code "107") (name "unconnected-(S1-Pad2)") (class "Default")
      (node (ref "S1") (pin "2") (pinfunction "2_2") (pintype "passive"))
    )
    (net (code "108") (name "unconnected-(S1-Pad3)") (class "Default")
      (node (ref "S1") (pin "3") (pinfunction "3_3") (pintype "passive"))
    )
  )
)
